# SparkFun_Qwiic_pHAT_Extension.net
KiCad netlist of a schematic drawn in EAGLE
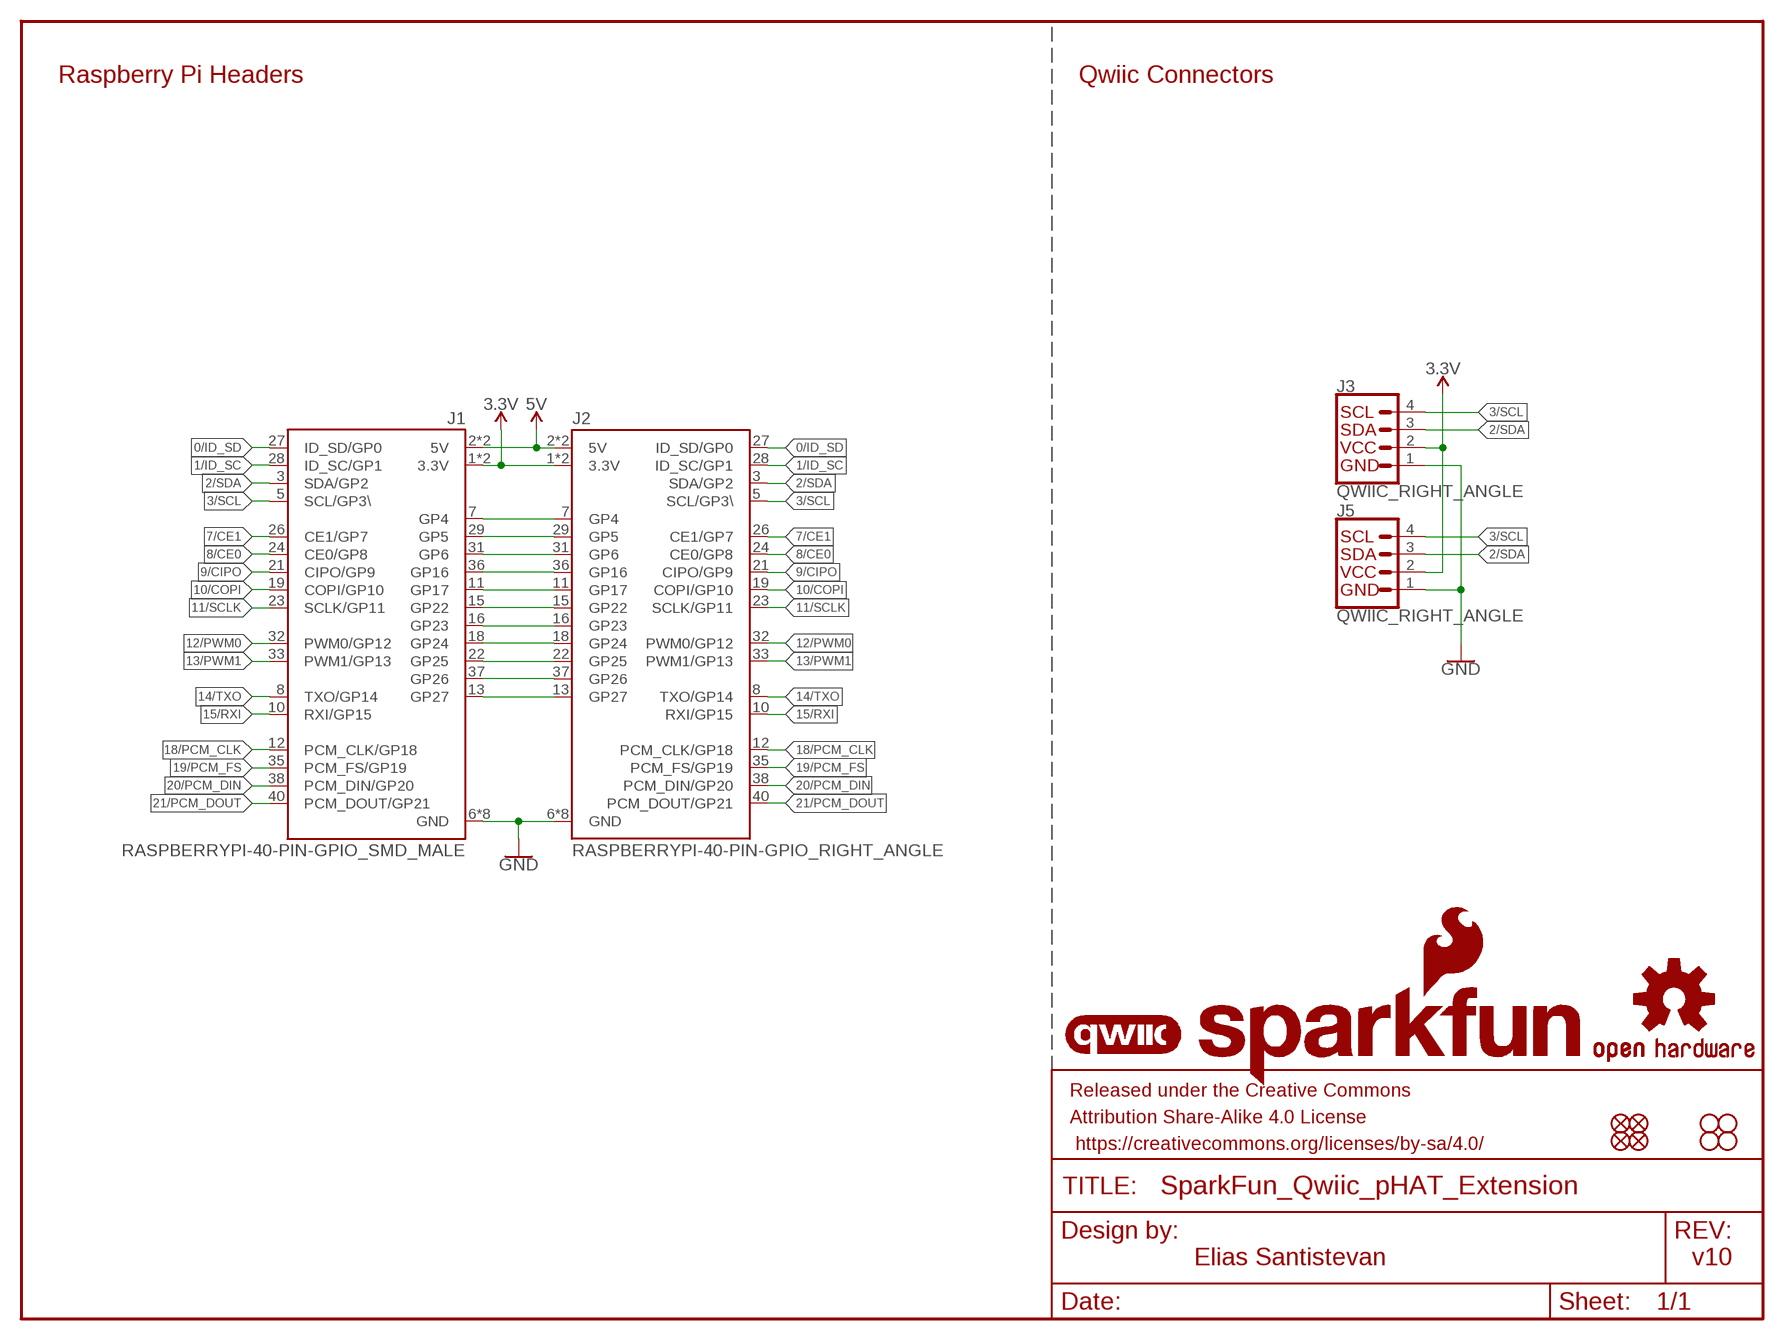
[diagram p0: schematic, sheet 1]

(export (version "E")
  (design (tool "Eeschema 10.0.6"))
  (components
    (comp (ref "FD1")
      (value "FIDUCIALUFIDUCIAL")
      (footprint "eagle-import:FIDUCIAL-MICRO")
      (libsource (lib "eagle-import") (part "FIDUCIALUFIDUCIAL"))
    )
    (comp (ref "FD2")
      (value "FIDUCIALUFIDUCIAL")
      (footprint "eagle-import:FIDUCIAL-MICRO")
      (libsource (lib "eagle-import") (part "FIDUCIALUFIDUCIAL"))
    )
    (comp (ref "FD3")
      (value "FIDUCIALUFIDUCIAL")
      (footprint "eagle-import:FIDUCIAL-MICRO")
      (libsource (lib "eagle-import") (part "FIDUCIALUFIDUCIAL"))
    )
    (comp (ref "FD4")
      (value "FIDUCIALUFIDUCIAL")
      (footprint "eagle-import:FIDUCIAL-MICRO")
      (libsource (lib "eagle-import") (part "FIDUCIALUFIDUCIAL"))
    )
    (comp (ref "FRAME1")
      (value "FRAME-LETTER")
      (footprint "eagle-import:CREATIVE_COMMONS")
      (libsource (lib "eagle-import") (part "FRAME-LETTER"))
    )
    (comp (ref "H1")
      (value "STAND-OFFTIGHT")
      (footprint "eagle-import:STAND-OFF-TIGHT")
      (libsource (lib "eagle-import") (part "STAND-OFFTIGHT"))
    )
    (comp (ref "H2")
      (value "STAND-OFFTIGHT")
      (footprint "eagle-import:STAND-OFF-TIGHT")
      (libsource (lib "eagle-import") (part "STAND-OFFTIGHT"))
    )
    (comp (ref "H3")
      (value "STAND-OFFTIGHT")
      (footprint "eagle-import:STAND-OFF-TIGHT")
      (libsource (lib "eagle-import") (part "STAND-OFFTIGHT"))
    )
    (comp (ref "H4")
      (value "STAND-OFFTIGHT")
      (footprint "eagle-import:STAND-OFF-TIGHT")
      (libsource (lib "eagle-import") (part "STAND-OFFTIGHT"))
    )
    (comp (ref "J1")
      (value "RASPBERRYPI-40-PIN-GPIO_SMD_MALE")
      (footprint "eagle-import:RASPBERRY_PI_HAT_40_PIN_SMD_MALE")
      (libsource (lib "eagle-import") (part "RASPBERRYPI-40-PIN-GPIO_SMD_MALE"))
    )
    (comp (ref "J2")
      (value "RASPBERRYPI-40-PIN-GPIO_RIGHT_ANGLE")
      (footprint "eagle-import:2X20_RIGHT_ANGLE")
      (libsource (lib "eagle-import") (part "RASPBERRYPI-40-PIN-GPIO_RIGHT_ANGLE"))
    )
    (comp (ref "J3")
      (value "QWIIC_RIGHT_ANGLE")
      (footprint "eagle-import:JST04_1MM_RA")
      (libsource (lib "eagle-import") (part "QWIIC_CONNECTORJS-1MM"))
    )
    (comp (ref "J5")
      (value "QWIIC_RIGHT_ANGLE")
      (footprint "eagle-import:JST04_1MM_RA")
      (libsource (lib "eagle-import") (part "QWIIC_CONNECTORJS-1MM"))
    )
    (comp (ref "LOGO1")
      (value "QWIIC_LOGO_5MM")
      (footprint "eagle-import:QWIIC_5MM")
      (libsource (lib "eagle-import") (part "QWIIC_LOGO_5MM"))
    )
    (comp (ref "LOGO2")
      (value "SFE_LOGO_NAME_FLAME.2_INCH")
      (footprint "eagle-import:SFE_LOGO_NAME_FLAME_.2")
      (libsource (lib "eagle-import") (part "SFE_LOGO_NAME_FLAME.2_INCH"))
    )
    (comp (ref "LOGO3")
      (value "OSHW-LOGOM")
      (footprint "eagle-import:OSHW-LOGO-M")
      (libsource (lib "eagle-import") (part "OSHW-LOGOM"))
    )
  )
  (nets
    (net (code "1") (name "0{slash}ID_SD") (class "Default")
      (node (ref "J1") (pin "27") (pinfunction "ID_SD/GP0_27") (pintype "bidirectional"))
      (node (ref "J2") (pin "27") (pinfunction "ID_SD/GP0_27") (pintype "bidirectional"))
    )
    (net (code "2") (name "1{slash}ID_SC") (class "Default")
      (node (ref "J1") (pin "28") (pinfunction "ID_SC/GP1_28") (pintype "bidirectional"))
      (node (ref "J2") (pin "28") (pinfunction "ID_SC/GP1_28") (pintype "bidirectional"))
    )
    (net (code "3") (name "2{slash}SDA") (class "Default")
      (node (ref "J1") (pin "3") (pinfunction "SDA/GP2_3") (pintype "bidirectional"))
      (node (ref "J2") (pin "3") (pinfunction "SDA/GP2_3") (pintype "bidirectional"))
      (node (ref "J3") (pin "3") (pinfunction "3_3") (pintype "passive"))
      (node (ref "J5") (pin "3") (pinfunction "3_3") (pintype "passive"))
    )
    (net (code "4") (name "3.3V") (class "Default")
      (node (ref "J1") (pin "1") (pinfunction "3.3V_1") (pintype "power_in"))
      (node (ref "J1") (pin "17") (pinfunction "3.3V_17") (pintype "power_in"))
      (node (ref "J2") (pin "1") (pinfunction "3.3V_1") (pintype "power_in"))
      (node (ref "J2") (pin "17") (pinfunction "3.3V_17") (pintype "power_in"))
      (node (ref "J3") (pin "2") (pinfunction "2_2") (pintype "power_in"))
      (node (ref "J5") (pin "2") (pinfunction "2_2") (pintype "power_in"))
    )
    (net (code "5") (name "3{slash}SCL") (class "Default")
      (node (ref "J1") (pin "5") (pinfunction "SCL/GP3\\_5") (pintype "bidirectional"))
      (node (ref "J2") (pin "5") (pinfunction "SCL/GP3\\_5") (pintype "bidirectional"))
      (node (ref "J3") (pin "4") (pinfunction "4_4") (pintype "passive"))
      (node (ref "J5") (pin "4") (pinfunction "4_4") (pintype "passive"))
    )
    (net (code "6") (name "5V") (class "Default")
      (node (ref "J1") (pin "2") (pinfunction "5V_2") (pintype "power_in"))
      (node (ref "J1") (pin "4") (pinfunction "5V_4") (pintype "power_in"))
      (node (ref "J2") (pin "2") (pinfunction "5V_2") (pintype "power_in"))
      (node (ref "J2") (pin "4") (pinfunction "5V_4") (pintype "power_in"))
    )
    (net (code "7") (name "7{slash}CE1") (class "Default")
      (node (ref "J1") (pin "26") (pinfunction "CE1/GP7_26") (pintype "output"))
      (node (ref "J2") (pin "26") (pinfunction "CE1/GP7_26") (pintype "output"))
    )
    (net (code "8") (name "8{slash}CE0") (class "Default")
      (node (ref "J1") (pin "24") (pinfunction "CE0/GP8_24") (pintype "output"))
      (node (ref "J2") (pin "24") (pinfunction "CE0/GP8_24") (pintype "output"))
    )
    (net (code "9") (name "9{slash}CIPO") (class "Default")
      (node (ref "J1") (pin "21") (pinfunction "CIPO/GP9_21") (pintype "input"))
      (node (ref "J2") (pin "21") (pinfunction "CIPO/GP9_21") (pintype "input"))
    )
    (net (code "10") (name "10{slash}COPI") (class "Default")
      (node (ref "J1") (pin "19") (pinfunction "COPI/GP10_19") (pintype "output"))
      (node (ref "J2") (pin "19") (pinfunction "COPI/GP10_19") (pintype "output"))
    )
    (net (code "11") (name "11{slash}SCLK") (class "Default")
      (node (ref "J1") (pin "23") (pinfunction "SCLK/GP11_23") (pintype "output"))
      (node (ref "J2") (pin "23") (pinfunction "SCLK/GP11_23") (pintype "output"))
    )
    (net (code "12") (name "12{slash}PWM0") (class "Default")
      (node (ref "J1") (pin "32") (pinfunction "PWM0/GP12_32") (pintype "bidirectional"))
      (node (ref "J2") (pin "32") (pinfunction "PWM0/GP12_32") (pintype "bidirectional"))
    )
    (net (code "13") (name "13{slash}PWM1") (class "Default")
      (node (ref "J1") (pin "33") (pinfunction "PWM1/GP13_33") (pintype "bidirectional"))
      (node (ref "J2") (pin "33") (pinfunction "PWM1/GP13_33") (pintype "bidirectional"))
    )
    (net (code "14") (name "14{slash}TXO") (class "Default")
      (node (ref "J1") (pin "8") (pinfunction "TXO/GP14_8") (pintype "output"))
      (node (ref "J2") (pin "8") (pinfunction "TXO/GP14_8") (pintype "output"))
    )
    (net (code "15") (name "15{slash}RXI") (class "Default")
      (node (ref "J1") (pin "10") (pinfunction "RXI/GP15_10") (pintype "input"))
      (node (ref "J2") (pin "10") (pinfunction "RXI/GP15_10") (pintype "input"))
    )
    (net (code "16") (name "18{slash}PCM_CLK") (class "Default")
      (node (ref "J1") (pin "12") (pinfunction "PCM_CLK/GP18_12") (pintype "bidirectional"))
      (node (ref "J2") (pin "12") (pinfunction "PCM_CLK/GP18_12") (pintype "bidirectional"))
    )
    (net (code "17") (name "19{slash}PCM_FS") (class "Default")
      (node (ref "J1") (pin "35") (pinfunction "PCM_FS/GP19_35") (pintype "bidirectional"))
      (node (ref "J2") (pin "35") (pinfunction "PCM_FS/GP19_35") (pintype "bidirectional"))
    )
    (net (code "18") (name "20{slash}PCM_DIN") (class "Default")
      (node (ref "J1") (pin "38") (pinfunction "PCM_DIN/GP20_38") (pintype "bidirectional"))
      (node (ref "J2") (pin "38") (pinfunction "PCM_DIN/GP20_38") (pintype "bidirectional"))
    )
    (net (code "19") (name "21{slash}PCM_DOUT") (class "Default")
      (node (ref "J1") (pin "40") (pinfunction "PCM_DOUT/GP21_40") (pintype "bidirectional"))
      (node (ref "J2") (pin "40") (pinfunction "PCM_DOUT/GP21_40") (pintype "bidirectional"))
    )
    (net (code "20") (name "GND") (class "Default")
      (node (ref "J1") (pin "14") (pinfunction "GND_14") (pintype "power_in"))
      (node (ref "J1") (pin "20") (pinfunction "GND_20") (pintype "power_in"))
      (node (ref "J1") (pin "25") (pinfunction "GND_25") (pintype "power_in"))
      (node (ref "J1") (pin "30") (pinfunction "GND_30") (pintype "power_in"))
      (node (ref "J1") (pin "34") (pinfunction "GND_34") (pintype "power_in"))
      (node (ref "J1") (pin "39") (pinfunction "GND_39") (pintype "power_in"))
      (node (ref "J1") (pin "6") (pinfunction "GND_6") (pintype "power_in"))
      (node (ref "J1") (pin "9") (pinfunction "GND_9") (pintype "power_in"))
      (node (ref "J2") (pin "14") (pinfunction "GND_14") (pintype "power_in"))
      (node (ref "J2") (pin "20") (pinfunction "GND_20") (pintype "power_in"))
      (node (ref "J2") (pin "25") (pinfunction "GND_25") (pintype "power_in"))
      (node (ref "J2") (pin "30") (pinfunction "GND_30") (pintype "power_in"))
      (node (ref "J2") (pin "34") (pinfunction "GND_34") (pintype "power_in"))
      (node (ref "J2") (pin "39") (pinfunction "GND_39") (pintype "power_in"))
      (node (ref "J2") (pin "6") (pinfunction "GND_6") (pintype "power_in"))
      (node (ref "J2") (pin "9") (pinfunction "GND_9") (pintype "power_in"))
      (node (ref "J3") (pin "1") (pinfunction "1_1") (pintype "power_in"))
      (node (ref "J5") (pin "1") (pinfunction "1_1") (pintype "power_in"))
    )
    (net (code "21") (name "Net-(J1-GP4)") (class "Default")
      (node (ref "J1") (pin "7") (pinfunction "GP4_7") (pintype "bidirectional"))
      (node (ref "J2") (pin "7") (pinfunction "GP4_7") (pintype "bidirectional"))
    )
    (net (code "22") (name "Net-(J1-GP5)") (class "Default")
      (node (ref "J1") (pin "29") (pinfunction "GP5_29") (pintype "bidirectional"))
      (node (ref "J2") (pin "29") (pinfunction "GP5_29") (pintype "bidirectional"))
    )
    (net (code "23") (name "Net-(J1-GP6)") (class "Default")
      (node (ref "J1") (pin "31") (pinfunction "GP6_31") (pintype "bidirectional"))
      (node (ref "J2") (pin "31") (pinfunction "GP6_31") (pintype "bidirectional"))
    )
    (net (code "24") (name "Net-(J1-GP16)") (class "Default")
      (node (ref "J1") (pin "36") (pinfunction "GP16_36") (pintype "bidirectional"))
      (node (ref "J2") (pin "36") (pinfunction "GP16_36") (pintype "bidirectional"))
    )
    (net (code "25") (name "Net-(J1-GP17)") (class "Default")
      (node (ref "J1") (pin "11") (pinfunction "GP17_11") (pintype "bidirectional"))
      (node (ref "J2") (pin "11") (pinfunction "GP17_11") (pintype "bidirectional"))
    )
    (net (code "26") (name "Net-(J1-GP22)") (class "Default")
      (node (ref "J1") (pin "15") (pinfunction "GP22_15") (pintype "bidirectional"))
      (node (ref "J2") (pin "15") (pinfunction "GP22_15") (pintype "bidirectional"))
    )
    (net (code "27") (name "Net-(J1-GP23)") (class "Default")
      (node (ref "J1") (pin "16") (pinfunction "GP23_16") (pintype "bidirectional"))
      (node (ref "J2") (pin "16") (pinfunction "GP23_16") (pintype "bidirectional"))
    )
    (net (code "28") (name "Net-(J1-GP24)") (class "Default")
      (node (ref "J1") (pin "18") (pinfunction "GP24_18") (pintype "bidirectional"))
      (node (ref "J2") (pin "18") (pinfunction "GP24_18") (pintype "bidirectional"))
    )
    (net (code "29") (name "Net-(J1-GP25)") (class "Default")
      (node (ref "J1") (pin "22") (pinfunction "GP25_22") (pintype "bidirectional"))
      (node (ref "J2") (pin "22") (pinfunction "GP25_22") (pintype "bidirectional"))
    )
    (net (code "30") (name "Net-(J1-GP26)") (class "Default")
      (node (ref "J1") (pin "37") (pinfunction "GP26_37") (pintype "bidirectional"))
      (node (ref "J2") (pin "37") (pinfunction "GP26_37") (pintype "bidirectional"))
    )
    (net (code "31") (name "Net-(J1-GP27)") (class "Default")
      (node (ref "J1") (pin "13") (pinfunction "GP27_13") (pintype "bidirectional"))
      (node (ref "J2") (pin "13") (pinfunction "GP27_13") (pintype "bidirectional"))
    )
  )
)
